# Sheet3.net
KiCad netlist of a schematic drawn in Altium Designer
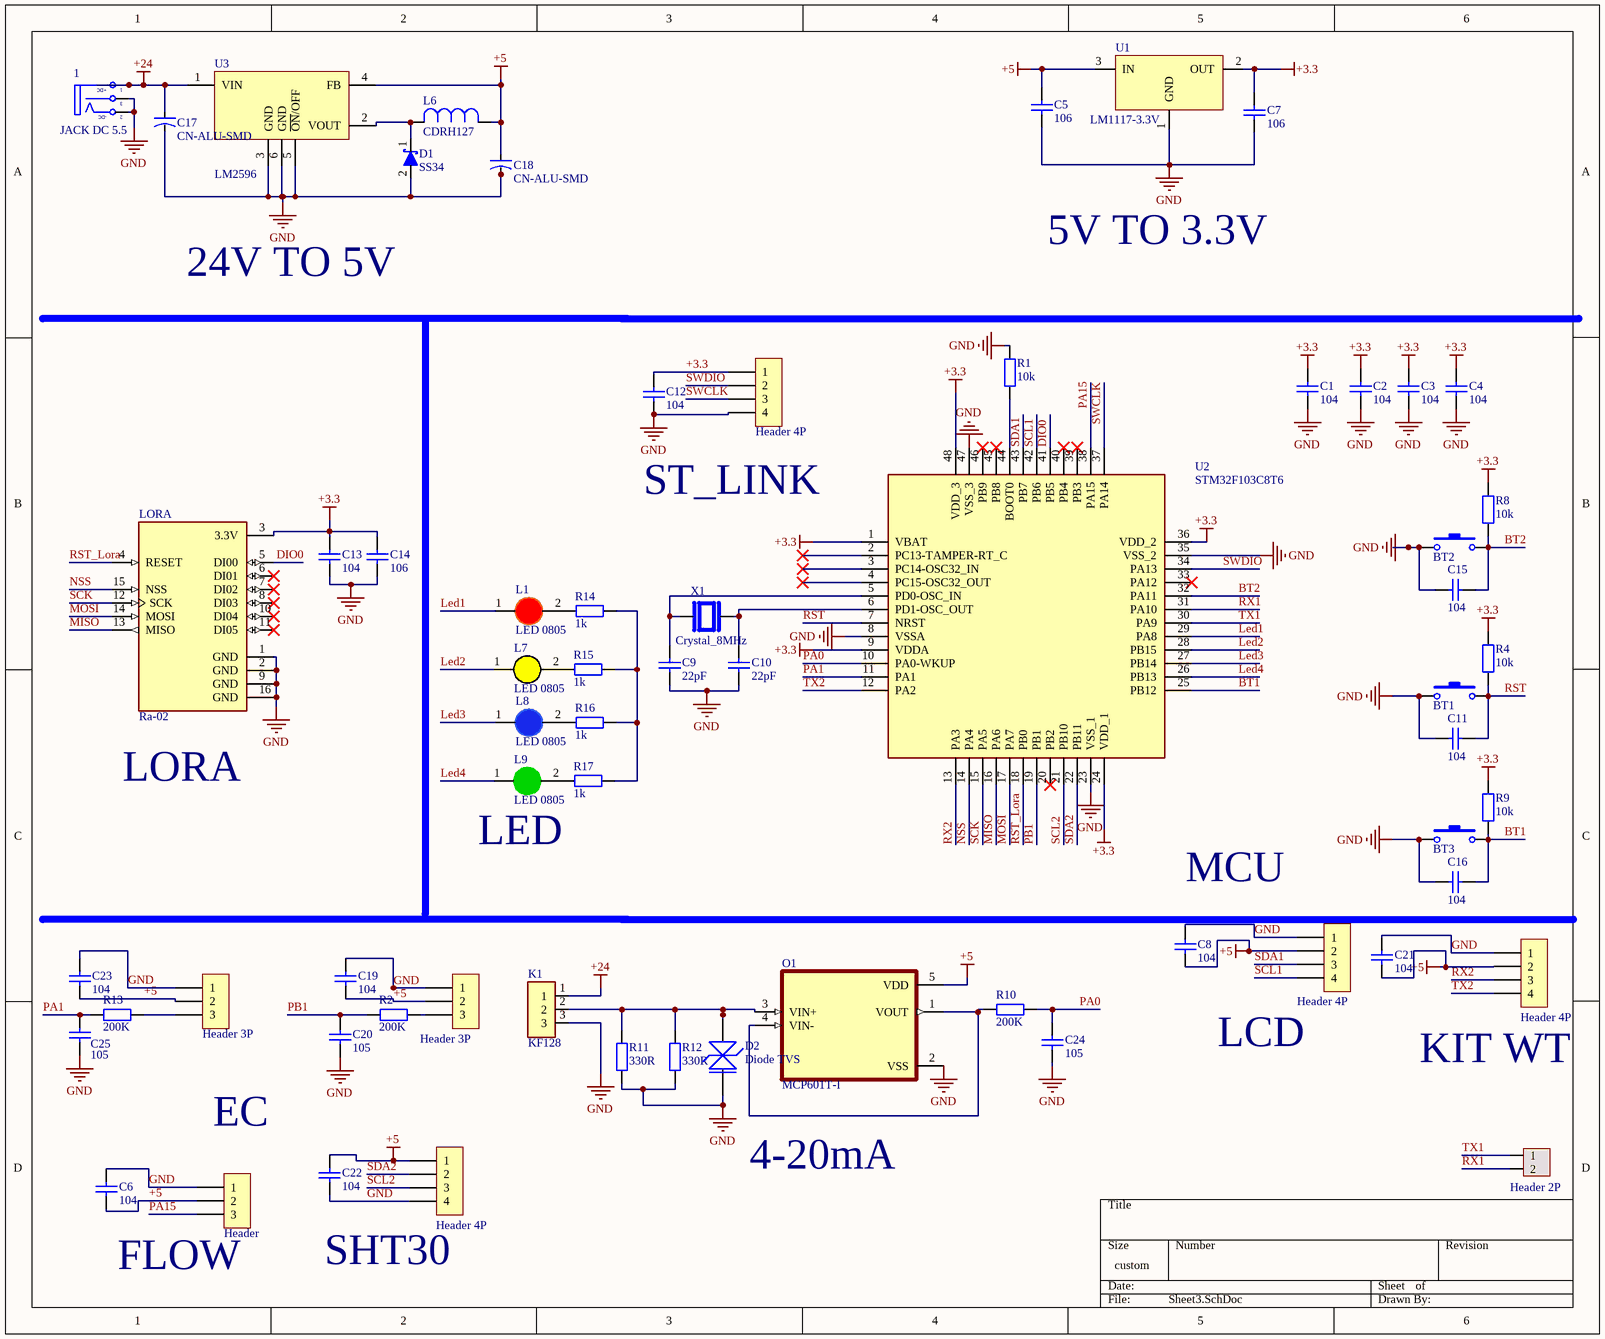
[diagram p0: Sheet3.SchDoc]

(export (version "E")
  (design (tool "Eeschema 10.0.6"))
  (components
    (comp (ref "1")
      (value "JACK DC 5.5")
      (footprint "JACK DC 5.5")
      (libsource (lib "Altium_Lib_by_KhueNguyenCreator") (part "JACK DC 5.5"))
    )
    (comp (ref "BT1")
      (value "Nut Nhan 2 Chan SMD 3x6x2.5")
      (footprint "Nut Nhan 2 Chan SMD 3x6x2.5")
      (libsource (lib "Altium_Lib_by_KhueNguyenCreator") (part "Nut Nhan 2 Chan SMD 3x6x2.5"))
    )
    (comp (ref "BT2")
      (value "Nut Nhan 2 Chan SMD 3x6x2.5")
      (footprint "Nut Nhan 2 Chan SMD 3x6x2.5")
      (libsource (lib "Altium_Lib_by_KhueNguyenCreator") (part "Nut Nhan 2 Chan SMD 3x6x2.5"))
    )
    (comp (ref "BT3")
      (value "Nut Nhan 2 Chan SMD 3x6x2.5")
      (footprint "Nut Nhan 2 Chan SMD 3x6x2.5")
      (libsource (lib "Altium_Lib_by_KhueNguyenCreator") (part "Nut Nhan 2 Chan SMD 3x6x2.5"))
    )
    (comp (ref "C1")
      (value "104")
      (footprint "tu 1206")
      (description "Dán")
      (libsource (lib "Altium_Lib_by_KhueNguyenCreator") (part "Tu 1206 104 50V 20%"))
    )
    (comp (ref "C2")
      (value "104")
      (footprint "tu 1206")
      (description "Dán")
      (libsource (lib "Altium_Lib_by_KhueNguyenCreator") (part "Tu 1206 104 50V 20%"))
    )
    (comp (ref "C3")
      (value "104")
      (footprint "tu 1206")
      (description "Dán")
      (libsource (lib "Altium_Lib_by_KhueNguyenCreator") (part "Tu 1206 104 50V 20%"))
    )
    (comp (ref "C4")
      (value "104")
      (footprint "tu 1206")
      (description "Dán")
      (libsource (lib "Altium_Lib_by_KhueNguyenCreator") (part "Tu 1206 104 50V 20%"))
    )
    (comp (ref "C5")
      (value "106")
      (footprint "tu 1206")
      (description "Dán")
      (libsource (lib "Altium_Lib_by_KhueNguyenCreator") (part "Tu 1206 106 16V 20%"))
    )
    (comp (ref "C6")
      (value "104")
      (footprint "tu 1206")
      (description "Dán")
      (libsource (lib "Altium_Lib_by_KhueNguyenCreator") (part "Tu 1206 104 50V 20%"))
    )
    (comp (ref "C7")
      (value "106")
      (footprint "tu 1206")
      (description "Dán")
      (libsource (lib "Altium_Lib_by_KhueNguyenCreator") (part "Tu 1206 106 16V 20%"))
    )
    (comp (ref "C8")
      (value "104")
      (footprint "tu 1206")
      (description "Dán")
      (libsource (lib "Altium_Lib_by_KhueNguyenCreator") (part "Tu 1206 104 50V 20%"))
    )
    (comp (ref "C9")
      (value "22pF")
      (footprint "tu 1206")
      (description "Dán")
      (libsource (lib "Altium_Lib_by_KhueNguyenCreator") (part "Tu 1206 104 50V 20%"))
    )
    (comp (ref "C10")
      (value "22pF")
      (footprint "tu 1206")
      (description "Dán")
      (libsource (lib "Altium_Lib_by_KhueNguyenCreator") (part "Tu 1206 104 50V 20%"))
    )
    (comp (ref "C11")
      (value "104")
      (footprint "tu 1206")
      (description "Dán")
      (libsource (lib "Altium_Lib_by_KhueNguyenCreator") (part "Tu 1206 104 50V 20%"))
    )
    (comp (ref "C12")
      (value "104")
      (footprint "tu 1206")
      (description "Dán")
      (libsource (lib "Altium_Lib_by_KhueNguyenCreator") (part "Tu 1206 104 50V 20%"))
    )
    (comp (ref "C13")
      (value "104")
      (footprint "tu 1206")
      (description "Dán")
      (libsource (lib "Altium_Lib_by_KhueNguyenCreator") (part "Tu 1206 104 50V 20%"))
    )
    (comp (ref "C14")
      (value "106")
      (footprint "tu 1206")
      (description "Dán")
      (libsource (lib "Altium_Lib_by_KhueNguyenCreator") (part "Tu 1206 106 16V 20%"))
    )
    (comp (ref "C15")
      (value "104")
      (footprint "tu 1206")
      (description "Dán")
      (libsource (lib "Altium_Lib_by_KhueNguyenCreator") (part "Tu 1206 104 50V 20%"))
    )
    (comp (ref "C16")
      (value "104")
      (footprint "tu 1206")
      (description "Dán")
      (libsource (lib "Altium_Lib_by_KhueNguyenCreator") (part "Tu 1206 104 50V 20%"))
    )
    (comp (ref "C17")
      (value "CN-ALU-SMD")
      (footprint "CAP-ALU-SMD-H")
      (description "Polarized Capacitor (Axial)")
      (fields (field (name "PUBLISHER") "Altium Limited"))
      (libsource (lib "TechMT.VN_Lib_Project v2") (part "CN-ALU-SMD"))
    )
    (comp (ref "C18")
      (value "CN-ALU-SMD")
      (footprint "CAP-ALU-SMD-D")
      (description "Polarized Capacitor (Axial)")
      (fields (field (name "PUBLISHER") "Altium Limited"))
      (libsource (lib "TechMT.VN_Lib_Project v2") (part "CN-ALU-SMD"))
    )
    (comp (ref "C19")
      (value "104")
      (footprint "tu 1206")
      (description "Dán")
      (libsource (lib "Altium_Lib_by_KhueNguyenCreator") (part "Tu 1206 104 50V 20%"))
    )
    (comp (ref "C20")
      (value "105")
      (footprint "tu 1206")
      (description "Dán")
      (libsource (lib "Altium_Lib_by_KhueNguyenCreator") (part "Tu 1206 105 50V 20%"))
    )
    (comp (ref "C21")
      (value "104")
      (footprint "tu 1206")
      (description "Dán")
      (libsource (lib "Altium_Lib_by_KhueNguyenCreator") (part "Tu 1206 104 50V 20%"))
    )
    (comp (ref "C22")
      (value "104")
      (footprint "tu 1206")
      (description "Dán")
      (libsource (lib "Altium_Lib_by_KhueNguyenCreator") (part "Tu 1206 104 50V 20%"))
    )
    (comp (ref "C23")
      (value "104")
      (footprint "tu 1206")
      (description "Dán")
      (libsource (lib "Altium_Lib_by_KhueNguyenCreator") (part "Tu 1206 104 50V 20%"))
    )
    (comp (ref "C24")
      (value "105")
      (footprint "tu 1206")
      (description "Dán")
      (libsource (lib "Altium_Lib_by_KhueNguyenCreator") (part "Tu 1206 105 50V 20%"))
    )
    (comp (ref "C25")
      (value "105")
      (footprint "tu 1206")
      (description "Dán")
      (libsource (lib "Altium_Lib_by_KhueNguyenCreator") (part "Tu 1206 105 50V 20%"))
    )
    (comp (ref "D1")
      (value "SS34")
      (footprint "DO-214AC")
      (description "Diode Schottky 40 V 5A Surface Mount DO-214AC (SMA)")
      (libsource (lib "My_lib") (part "SS54"))
    )
    (comp (ref "D2")
      (value "Diode TVS")
      (footprint "MinhTien_PCBLib:DO-214AC")
      (description "TVS Diodes - Transient Voltage Suppressors")
      (fields (field (name "PUBLISHER") "Altium Limited"))
      (libsource (lib "MinhTien_SCHLib") (part "Diode TVS"))
    )
    (comp (ref "FLOW")
      (value "Header")
      (footprint "XH2.54M-3")
      (description "Cắm")
      (libsource (lib "Altium_Lib_by_KhueNguyenCreator") (part "Header 3P 2.54 Duc Thang"))
    )
    (comp (ref "H1")
      (value "Header 2P")
      (footprint "XH2.54M-2")
      (description "Cắm")
      (libsource (lib "Altium_Lib_by_KhueNguyenCreator") (part "Header 2P 2.54 Duc Thang"))
    )
    (comp (ref "K1")
      (value "KF128")
      (footprint "KF128_3V")
      (description "KF128-3-V Domino 3 Chân Thẳng 2.54mm 150V 6A Hàn PCB")
      (libsource (lib "My_lib") (part "KF128_3V"))
    )
    (comp (ref "KIT")
      (value "Header 4P")
      (footprint "XH2.54M-4")
      (description "Cắm")
      (libsource (lib "Altium_Lib_by_KhueNguyenCreator") (part "Header 4P 2.54 Duc Thang"))
    )
    (comp (ref "L1")
      (value "LED 0805")
      (footprint "LED-1206-Red")
      (description "Dán")
      (libsource (lib "Altium_Lib_by_KhueNguyenCreator") (part "LED 1206 Do"))
    )
    (comp (ref "L6")
      (value "CDRH127")
      (footprint "33uH")
      (description "33uH - Inductor 4.2 A")
      (libsource (lib "My_lib") (part "CDRH127"))
    )
    (comp (ref "L7")
      (value "LED 0805")
      (footprint "LED-1206-Yellow")
      (description "Dán")
      (libsource (lib "Altium_Lib_by_KhueNguyenCreator") (part "LED 1206 Vang"))
    )
    (comp (ref "L8")
      (value "LED 0805")
      (footprint "LED-1206-Blue")
      (description "Dán")
      (libsource (lib "Altium_Lib_by_KhueNguyenCreator") (part "LED 1206 Xanh Duong"))
    )
    (comp (ref "L9")
      (value "LED 0805")
      (footprint "LED-1206-Green")
      (description "Dán")
      (libsource (lib "Altium_Lib_by_KhueNguyenCreator") (part "LED 1206 Xanh La"))
    )
    (comp (ref "LCD")
      (value "Header 4P")
      (footprint "XH2.54M-4")
      (description "Cắm")
      (libsource (lib "Altium_Lib_by_KhueNguyenCreator") (part "Header 4P 2.54 Duc Thang"))
    )
    (comp (ref "LORA")
      (value "Ra-02")
      (footprint "Sx1278")
      (description "Lora sx1278")
      (libsource (lib "My_lib") (part "Ra-02"))
    )
    (comp (ref "O1")
      (value "MCP601T-I")
      (footprint "MCP601T-I")
      (description "MCP601T-I/OT IC OPAMP General Purpose Amplifier 1 Circuit 2.8MHz, 5-SOT-23")
      (libsource (lib "My_lib") (part "MCP601T-I"))
    )
    (comp (ref "R1")
      (value "10k")
      (footprint "tro smd 1206")
      (description "Dán")
      (libsource (lib "Altium_Lib_by_KhueNguyenCreator") (part "Tro 1206 1% 10k"))
    )
    (comp (ref "R2")
      (value "200K")
      (footprint "tro smd 1206")
      (description "Dán")
      (libsource (lib "Altium_Lib_by_KhueNguyenCreator") (part "Tro 1206 5% 100K"))
    )
    (comp (ref "R4")
      (value "10k")
      (footprint "tro smd 1206")
      (description "Dán")
      (libsource (lib "Altium_Lib_by_KhueNguyenCreator") (part "Tro 1206 1% 10k"))
    )
    (comp (ref "R8")
      (value "10k")
      (footprint "tro smd 1206")
      (description "Dán")
      (libsource (lib "Altium_Lib_by_KhueNguyenCreator") (part "Tro 1206 1% 10k"))
    )
    (comp (ref "R9")
      (value "10k")
      (footprint "tro smd 1206")
      (description "Dán")
      (libsource (lib "Altium_Lib_by_KhueNguyenCreator") (part "Tro 1206 1% 10k"))
    )
    (comp (ref "R10")
      (value "200K")
      (footprint "tro smd 1206")
      (description "Dán")
      (libsource (lib "Altium_Lib_by_KhueNguyenCreator") (part "Tro 1206 5% 100K"))
    )
    (comp (ref "R11")
      (value "330R")
      (footprint "tro smd 1206")
      (description "Dán")
      (libsource (lib "Altium_Lib_by_KhueNguyenCreator") (part "Tro 1206 1% 10R"))
    )
    (comp (ref "R12")
      (value "330R")
      (footprint "tro smd 1206")
      (description "Dán")
      (libsource (lib "Altium_Lib_by_KhueNguyenCreator") (part "Tro 1206 1% 10R"))
    )
    (comp (ref "R13")
      (value "200K")
      (footprint "tro smd 1206")
      (description "Dán")
      (libsource (lib "Altium_Lib_by_KhueNguyenCreator") (part "Tro 1206 5% 100K"))
    )
    (comp (ref "R14")
      (value "1k")
      (footprint "Tro smd 1206")
      (description "Dán")
      (libsource (lib "Altium_Lib_by_KhueNguyenCreator") (part "Tro 1206 5% 390R"))
    )
    (comp (ref "R15")
      (value "1k")
      (footprint "Tro smd 1206")
      (description "Dán")
      (libsource (lib "Altium_Lib_by_KhueNguyenCreator") (part "Tro 1206 5% 390R"))
    )
    (comp (ref "R16")
      (value "1k")
      (footprint "Tro smd 1206")
      (description "Dán")
      (libsource (lib "Altium_Lib_by_KhueNguyenCreator") (part "Tro 1206 5% 390R"))
    )
    (comp (ref "R17")
      (value "1k")
      (footprint "Tro smd 1206")
      (description "Dán")
      (libsource (lib "Altium_Lib_by_KhueNguyenCreator") (part "Tro 1206 5% 390R"))
    )
    (comp (ref "SAL")
      (value "Header 3P")
      (footprint "XH2.54M-3")
      (description "Cắm")
      (libsource (lib "Altium_Lib_by_KhueNguyenCreator") (part "Header 3P 2.54 Duc Thang"))
    )
    (comp (ref "SHT3x")
      (value "Header 4P")
      (footprint "XH2.54M-4")
      (description "Cắm")
      (libsource (lib "Altium_Lib_by_KhueNguyenCreator") (part "Header 4P 2.54 Duc Thang"))
    )
    (comp (ref "ST")
      (value "Header 4P")
      (footprint "XH2.54M-4")
      (description "Cắm")
      (libsource (lib "Altium_Lib_by_KhueNguyenCreator") (part "Header 4P 2.54 Duc Thang"))
    )
    (comp (ref "TEMP_W")
      (value "Header 3P")
      (footprint "XH2.54M-3")
      (description "Cắm")
      (libsource (lib "Altium_Lib_by_KhueNguyenCreator") (part "Header 3P 2.54 Duc Thang"))
    )
    (comp (ref "U1")
      (value "LM1117-3.3V")
      (footprint "SOT223")
      (description "800mA Low-Dropout Linear Regulator")
      (fields (field (name "CREATOR") "Nguyen Ba Bien"))
      (libsource (lib "TechMT.VN_Lib_Project v2") (part "LM1117"))
    )
    (comp (ref "U2")
      (value "STM32F103C8T6")
      (footprint "LQFP-48_19.6_393_58X11_SMD")
      (description "ARM® Cortex®-M3 STM32F1 Microcontroller IC 32-Bit 72MHz 64KB (64K x 8) FLASH 48-LQFP (7x7)")
      (fields (field (name "MANUFACTURER") "STMicroelectronics"))
      (libsource (lib "Altium_Lib_by_KhueNguyenCreator") (part "IC_STM32F103C8T6"))
    )
    (comp (ref "U3")
      (value "LM2596")
      (footprint "MinhTien_PcbLib:TO263-5")
      (description "1A Regulator")
      (libsource (lib "MinhTien_SCHLib") (part "LM2596"))
    )
    (comp (ref "X1")
      (value "Crystal_8MHz")
      (footprint "XTAL_8MHz")
      (description "8MHz")
      (libsource (lib "My_lib") (part "Crystal_8MHz"))
    )
  )
  (nets
    (net (code "1") (name "+3.3") (class "Default")
      (node (ref "C1") (pin "1") (pinfunction "1_1") (pintype "passive"))
      (node (ref "C12") (pin "2") (pinfunction "2_2") (pintype "passive"))
      (node (ref "C13") (pin "1") (pinfunction "1_1") (pintype "passive"))
      (node (ref "C14") (pin "1") (pinfunction "1_1") (pintype "passive"))
      (node (ref "C2") (pin "1") (pinfunction "1_1") (pintype "passive"))
      (node (ref "C3") (pin "1") (pinfunction "1_1") (pintype "passive"))
      (node (ref "C4") (pin "1") (pinfunction "1_1") (pintype "passive"))
      (node (ref "C7") (pin "1") (pinfunction "1_1") (pintype "passive"))
      (node (ref "LORA") (pin "3") (pinfunction "3.3V_3") (pintype "power_in"))
      (node (ref "R4") (pin "2") (pinfunction "2_2") (pintype "passive"))
      (node (ref "R8") (pin "2") (pinfunction "2_2") (pintype "passive"))
      (node (ref "R9") (pin "2") (pinfunction "2_2") (pintype "passive"))
      (node (ref "ST") (pin "1") (pinfunction "1_1") (pintype "passive"))
      (node (ref "U1") (pin "2") (pinfunction "OUT_2") (pintype "passive"))
      (node (ref "U2") (pin "1") (pinfunction "VBAT_1") (pintype "passive"))
      (node (ref "U2") (pin "24") (pinfunction "VDD_1_24") (pintype "passive"))
      (node (ref "U2") (pin "36") (pinfunction "VDD_2_36") (pintype "passive"))
      (node (ref "U2") (pin "48") (pinfunction "VDD_3_48") (pintype "passive"))
      (node (ref "U2") (pin "9") (pinfunction "VDDA_9") (pintype "passive"))
    )
    (net (code "2") (name "+5") (class "Default")
      (node (ref "C18") (pin "1") (pinfunction "1_1") (pintype "passive"))
      (node (ref "C19") (pin "2") (pinfunction "2_2") (pintype "passive"))
      (node (ref "C21") (pin "2") (pinfunction "2_2") (pintype "passive"))
      (node (ref "C22") (pin "1") (pinfunction "1_1") (pintype "passive"))
      (node (ref "C23") (pin "2") (pinfunction "2_2") (pintype "passive"))
      (node (ref "C5") (pin "1") (pinfunction "1_1") (pintype "passive"))
      (node (ref "C6") (pin "2") (pinfunction "2_2") (pintype "passive"))
      (node (ref "C8") (pin "2") (pinfunction "2_2") (pintype "passive"))
      (node (ref "FLOW") (pin "2") (pinfunction "2_2") (pintype "passive"))
      (node (ref "KIT") (pin "2") (pinfunction "2_2") (pintype "passive"))
      (node (ref "L6") (pin "1") (pinfunction "1_1") (pintype "passive"))
      (node (ref "LCD") (pin "2") (pinfunction "2_2") (pintype "passive"))
      (node (ref "O1") (pin "5") (pinfunction "VDD_5") (pintype "power_in"))
      (node (ref "SAL") (pin "2") (pinfunction "2_2") (pintype "passive"))
      (node (ref "SHT3x") (pin "1") (pinfunction "1_1") (pintype "passive"))
      (node (ref "TEMP_W") (pin "2") (pinfunction "2_2") (pintype "passive"))
      (node (ref "U1") (pin "3") (pinfunction "IN_3") (pintype "passive"))
      (node (ref "U3") (pin "4") (pinfunction "FB_4") (pintype "passive"))
    )
    (net (code "3") (name "+24") (class "Default")
      (node (ref "1") (pin "1") (pinfunction "T_1") (pintype "passive"))
      (node (ref "C17") (pin "1") (pinfunction "1_1") (pintype "passive"))
      (node (ref "K1") (pin "1") (pinfunction "1_1") (pintype "passive"))
      (node (ref "U3") (pin "1") (pinfunction "VIN_1") (pintype "passive"))
    )
    (net (code "4") (name "/BT1") (class "Default")
      (node (ref "BT3") (pin "2") (pinfunction "2_2") (pintype "passive"))
      (node (ref "C16") (pin "2") (pinfunction "2_2") (pintype "passive"))
      (node (ref "R9") (pin "1") (pinfunction "1_1") (pintype "passive"))
      (node (ref "U2") (pin "25") (pinfunction "PB12_25") (pintype "passive"))
    )
    (net (code "5") (name "/BT2") (class "Default")
      (node (ref "BT2") (pin "2") (pinfunction "2_2") (pintype "passive"))
      (node (ref "C15") (pin "2") (pinfunction "2_2") (pintype "passive"))
      (node (ref "R8") (pin "1") (pinfunction "1_1") (pintype "passive"))
      (node (ref "U2") (pin "32") (pinfunction "PA11_32") (pintype "passive"))
    )
    (net (code "6") (name "/DIO0") (class "Default")
      (node (ref "LORA") (pin "5") (pinfunction "DI00_5") (pintype "bidirectional"))
      (node (ref "U2") (pin "41") (pinfunction "PB5_41") (pintype "passive"))
    )
    (net (code "7") (name "/Led1") (class "Default")
      (node (ref "L1") (pin "1") (pinfunction "A_1") (pintype "passive"))
      (node (ref "U2") (pin "29") (pinfunction "PA8_29") (pintype "passive"))
    )
    (net (code "8") (name "/Led2") (class "Default")
      (node (ref "L7") (pin "1") (pinfunction "A_1") (pintype "passive"))
      (node (ref "U2") (pin "28") (pinfunction "PB15_28") (pintype "passive"))
    )
    (net (code "9") (name "/Led3") (class "Default")
      (node (ref "L8") (pin "1") (pinfunction "A_1") (pintype "passive"))
      (node (ref "U2") (pin "27") (pinfunction "PB14_27") (pintype "passive"))
    )
    (net (code "10") (name "/Led4") (class "Default")
      (node (ref "L9") (pin "1") (pinfunction "A_1") (pintype "passive"))
      (node (ref "U2") (pin "26") (pinfunction "PB13_26") (pintype "passive"))
    )
    (net (code "11") (name "/MISO") (class "Default")
      (node (ref "LORA") (pin "13") (pinfunction "MISO_13") (pintype "output"))
      (node (ref "U2") (pin "16") (pinfunction "PA6_16") (pintype "passive"))
    )
    (net (code "12") (name "/MOSI") (class "Default")
      (node (ref "LORA") (pin "14") (pinfunction "MOSI_14") (pintype "input"))
      (node (ref "U2") (pin "17") (pinfunction "PA7_17") (pintype "passive"))
    )
    (net (code "13") (name "/NSS") (class "Default")
      (node (ref "LORA") (pin "15") (pinfunction "NSS_15") (pintype "input"))
      (node (ref "U2") (pin "14") (pinfunction "PA4_14") (pintype "passive"))
    )
    (net (code "14") (name "/PA0") (class "Default")
      (node (ref "C24") (pin "1") (pinfunction "1_1") (pintype "passive"))
      (node (ref "R10") (pin "2") (pinfunction "2_2") (pintype "passive"))
      (node (ref "U2") (pin "10") (pinfunction "PA0-WKUP_10") (pintype "passive"))
    )
    (net (code "15") (name "/PA1") (class "Default")
      (node (ref "C25") (pin "1") (pinfunction "1_1") (pintype "passive"))
      (node (ref "R13") (pin "1") (pinfunction "1_1") (pintype "passive"))
      (node (ref "U2") (pin "11") (pinfunction "PA1_11") (pintype "passive"))
    )
    (net (code "16") (name "/PA15") (class "Default")
      (node (ref "FLOW") (pin "3") (pinfunction "3_3") (pintype "passive"))
      (node (ref "U2") (pin "38") (pinfunction "PA15_38") (pintype "passive"))
    )
    (net (code "17") (name "/PB1") (class "Default")
      (node (ref "C20") (pin "1") (pinfunction "1_1") (pintype "passive"))
      (node (ref "R2") (pin "1") (pinfunction "1_1") (pintype "passive"))
      (node (ref "U2") (pin "19") (pinfunction "PB1_19") (pintype "passive"))
    )
    (net (code "18") (name "/RST") (class "Default")
      (node (ref "BT1") (pin "2") (pinfunction "2_2") (pintype "passive"))
      (node (ref "C11") (pin "2") (pinfunction "2_2") (pintype "passive"))
      (node (ref "R4") (pin "1") (pinfunction "1_1") (pintype "passive"))
      (node (ref "U2") (pin "7") (pinfunction "NRST_7") (pintype "passive"))
    )
    (net (code "19") (name "/RST_Lora") (class "Default")
      (node (ref "LORA") (pin "4") (pinfunction "RESET_4") (pintype "input"))
      (node (ref "U2") (pin "18") (pinfunction "PB0_18") (pintype "passive"))
    )
    (net (code "20") (name "/RX1") (class "Default")
      (node (ref "H1") (pin "2") (pinfunction "2_2") (pintype "passive"))
      (node (ref "U2") (pin "31") (pinfunction "PA10_31") (pintype "passive"))
    )
    (net (code "21") (name "/RX2") (class "Default")
      (node (ref "KIT") (pin "3") (pinfunction "3_3") (pintype "passive"))
      (node (ref "U2") (pin "13") (pinfunction "PA3_13") (pintype "passive"))
    )
    (net (code "22") (name "/SCK") (class "Default")
      (node (ref "LORA") (pin "12") (pinfunction "SCK_12") (pintype "input"))
      (node (ref "U2") (pin "15") (pinfunction "PA5_15") (pintype "passive"))
    )
    (net (code "23") (name "/SCL1") (class "Default")
      (node (ref "LCD") (pin "4") (pinfunction "4_4") (pintype "passive"))
      (node (ref "U2") (pin "42") (pinfunction "PB6_42") (pintype "passive"))
    )
    (net (code "24") (name "/SCL2") (class "Default")
      (node (ref "SHT3x") (pin "3") (pinfunction "3_3") (pintype "passive"))
      (node (ref "U2") (pin "21") (pinfunction "PB10_21") (pintype "passive"))
    )
    (net (code "25") (name "/SDA1") (class "Default")
      (node (ref "LCD") (pin "3") (pinfunction "3_3") (pintype "passive"))
      (node (ref "U2") (pin "43") (pinfunction "PB7_43") (pintype "passive"))
    )
    (net (code "26") (name "/SDA2") (class "Default")
      (node (ref "SHT3x") (pin "2") (pinfunction "2_2") (pintype "passive"))
      (node (ref "U2") (pin "22") (pinfunction "PB11_22") (pintype "passive"))
    )
    (net (code "27") (name "/SWCLK") (class "Default")
      (node (ref "ST") (pin "3") (pinfunction "3_3") (pintype "passive"))
      (node (ref "U2") (pin "37") (pinfunction "PA14_37") (pintype "passive"))
    )
    (net (code "28") (name "/SWDIO") (class "Default")
      (node (ref "ST") (pin "2") (pinfunction "2_2") (pintype "passive"))
      (node (ref "U2") (pin "34") (pinfunction "PA13_34") (pintype "passive"))
    )
    (net (code "29") (name "/TX1") (class "Default")
      (node (ref "H1") (pin "1") (pinfunction "1_1") (pintype "passive"))
      (node (ref "U2") (pin "30") (pinfunction "PA9_30") (pintype "passive"))
    )
    (net (code "30") (name "/TX2") (class "Default")
      (node (ref "KIT") (pin "4") (pinfunction "4_4") (pintype "passive"))
      (node (ref "U2") (pin "12") (pinfunction "PA2_12") (pintype "passive"))
    )
    (net (code "31") (name "GND") (class "Default")
      (node (ref "1") (pin "2") (pinfunction "TN_2") (pintype "passive"))
      (node (ref "1") (pin "3") (pinfunction "S_3") (pintype "power_in"))
      (node (ref "BT1") (pin "1") (pinfunction "1_1") (pintype "passive"))
      (node (ref "BT2") (pin "1") (pinfunction "1_1") (pintype "passive"))
      (node (ref "BT3") (pin "1") (pinfunction "1_1") (pintype "passive"))
      (node (ref "C1") (pin "2") (pinfunction "2_2") (pintype "passive"))
      (node (ref "C10") (pin "2") (pinfunction "2_2") (pintype "passive"))
      (node (ref "C11") (pin "1") (pinfunction "1_1") (pintype "passive"))
      (node (ref "C12") (pin "1") (pinfunction "1_1") (pintype "passive"))
      (node (ref "C13") (pin "2") (pinfunction "2_2") (pintype "passive"))
      (node (ref "C14") (pin "2") (pinfunction "2_2") (pintype "passive"))
      (node (ref "C15") (pin "1") (pinfunction "1_1") (pintype "passive"))
      (node (ref "C16") (pin "1") (pinfunction "1_1") (pintype "passive"))
      (node (ref "C17") (pin "2") (pinfunction "2_2") (pintype "passive"))
      (node (ref "C18") (pin "2") (pinfunction "2_2") (pintype "passive"))
      (node (ref "C19") (pin "1") (pinfunction "1_1") (pintype "passive"))
      (node (ref "C2") (pin "2") (pinfunction "2_2") (pintype "passive"))
      (node (ref "C20") (pin "2") (pinfunction "2_2") (pintype "passive"))
      (node (ref "C21") (pin "1") (pinfunction "1_1") (pintype "passive"))
      (node (ref "C22") (pin "2") (pinfunction "2_2") (pintype "passive"))
      (node (ref "C23") (pin "1") (pinfunction "1_1") (pintype "passive"))
      (node (ref "C24") (pin "2") (pinfunction "2_2") (pintype "passive"))
      (node (ref "C25") (pin "2") (pinfunction "2_2") (pintype "passive"))
      (node (ref "C3") (pin "2") (pinfunction "2_2") (pintype "passive"))
      (node (ref "C4") (pin "2") (pinfunction "2_2") (pintype "passive"))
      (node (ref "C5") (pin "2") (pinfunction "2_2") (pintype "passive"))
      (node (ref "C6") (pin "1") (pinfunction "1_1") (pintype "passive"))
      (node (ref "C7") (pin "2") (pinfunction "2_2") (pintype "passive"))
      (node (ref "C8") (pin "1") (pinfunction "1_1") (pintype "passive"))
      (node (ref "C9") (pin "2") (pinfunction "2_2") (pintype "passive"))
      (node (ref "D1") (pin "2") (pinfunction "A_2") (pintype "bidirectional"))
      (node (ref "D2") (pin "2") (pinfunction "2_2") (pintype "power_in"))
      (node (ref "FLOW") (pin "1") (pinfunction "1_1") (pintype "passive"))
      (node (ref "K1") (pin "3") (pinfunction "3_3") (pintype "passive"))
      (node (ref "KIT") (pin "1") (pinfunction "1_1") (pintype "passive"))
      (node (ref "LCD") (pin "1") (pinfunction "1_1") (pintype "passive"))
      (node (ref "LORA") (pin "1") (pinfunction "GND_1") (pintype "power_in"))
      (node (ref "LORA") (pin "16") (pinfunction "GND_16") (pintype "power_in"))
      (node (ref "LORA") (pin "2") (pinfunction "GND_2") (pintype "power_in"))
      (node (ref "LORA") (pin "9") (pinfunction "GND_9") (pintype "power_in"))
      (node (ref "O1") (pin "2") (pinfunction "VSS_2") (pintype "power_in"))
      (node (ref "R1") (pin "2") (pinfunction "2_2") (pintype "passive"))
      (node (ref "R11") (pin "2") (pinfunction "2_2") (pintype "passive"))
      (node (ref "R12") (pin "2") (pinfunction "2_2") (pintype "passive"))
      (node (ref "SAL") (pin "1") (pinfunction "1_1") (pintype "passive"))
      (node (ref "SHT3x") (pin "4") (pinfunction "4_4") (pintype "passive"))
      (node (ref "ST") (pin "4") (pinfunction "4_4") (pintype "passive"))
      (node (ref "TEMP_W") (pin "1") (pinfunction "1_1") (pintype "passive"))
      (node (ref "U1") (pin "1") (pinfunction "GND_1") (pintype "passive"))
      (node (ref "U2") (pin "23") (pinfunction "VSS_1_23") (pintype "passive"))
      (node (ref "U2") (pin "35") (pinfunction "VSS_2_35") (pintype "passive"))
      (node (ref "U2") (pin "47") (pinfunction "VSS_3_47") (pintype "passive"))
      (node (ref "U2") (pin "8") (pinfunction "VSSA_8") (pintype "passive"))
      (node (ref "U3") (pin "3") (pinfunction "GND_3") (pintype "passive"))
      (node (ref "U3") (pin "5") (pinfunction "~{ON}/OFF_5") (pintype "passive"))
      (node (ref "U3") (pin "6") (pinfunction "GND_6") (pintype "passive"))
    )
    (net (code "32") (name "Net-(D1-K)") (class "Default")
      (node (ref "D1") (pin "1") (pinfunction "K_1") (pintype "bidirectional"))
      (node (ref "L6") (pin "2") (pinfunction "2_2") (pintype "passive"))
      (node (ref "U3") (pin "2") (pinfunction "VOUT_2") (pintype "passive"))
    )
    (net (code "33") (name "Net-(L1-K)") (class "Default")
      (node (ref "L1") (pin "2") (pinfunction "K_2") (pintype "passive"))
      (node (ref "R14") (pin "2") (pinfunction "2_2") (pintype "passive"))
    )
    (net (code "34") (name "Net-(L7-K)") (class "Default")
      (node (ref "L7") (pin "2") (pinfunction "K_2") (pintype "passive"))
      (node (ref "R15") (pin "1") (pinfunction "1_1") (pintype "passive"))
    )
    (net (code "35") (name "Net-(L8-K)") (class "Default")
      (node (ref "L8") (pin "2") (pinfunction "K_2") (pintype "passive"))
      (node (ref "R16") (pin "1") (pinfunction "1_1") (pintype "passive"))
    )
    (net (code "36") (name "Net-(L9-K)") (class "Default")
      (node (ref "L9") (pin "2") (pinfunction "K_2") (pintype "passive"))
      (node (ref "R17") (pin "1") (pinfunction "1_1") (pintype "passive"))
    )
    (net (code "37") (name "Net-(O1-VIN+)") (class "Default")
      (node (ref "D2") (pin "1") (pinfunction "1_1") (pintype "power_in"))
      (node (ref "K1") (pin "2") (pinfunction "2_2") (pintype "passive"))
      (node (ref "O1") (pin "3") (pinfunction "VIN+_3") (pintype "input"))
      (node (ref "R11") (pin "1") (pinfunction "1_1") (pintype "passive"))
      (node (ref "R12") (pin "1") (pinfunction "1_1") (pintype "passive"))
    )
    (net (code "38") (name "Net-(O1-VIN-)") (class "Default")
      (node (ref "O1") (pin "1") (pinfunction "VOUT_1") (pintype "output"))
      (node (ref "O1") (pin "4") (pinfunction "VIN-_4") (pintype "input"))
      (node (ref "R10") (pin "1") (pinfunction "1_1") (pintype "passive"))
    )
    (net (code "39") (name "Net-(R2-Pad2)") (class "Default")
      (node (ref "R2") (pin "2") (pinfunction "2_2") (pintype "passive"))
      (node (ref "SAL") (pin "3") (pinfunction "3_3") (pintype "passive"))
    )
    (net (code "40") (name "Net-(R13-Pad2)") (class "Default")
      (node (ref "R13") (pin "2") (pinfunction "2_2") (pintype "passive"))
      (node (ref "TEMP_W") (pin "3") (pinfunction "3_3") (pintype "passive"))
    )
    (net (code "41") (name "Net-(R14-Pad1)") (class "Default")
      (node (ref "R14") (pin "1") (pinfunction "1_1") (pintype "passive"))
      (node (ref "R15") (pin "2") (pinfunction "2_2") (pintype "passive"))
      (node (ref "R16") (pin "2") (pinfunction "2_2") (pintype "passive"))
      (node (ref "R17") (pin "2") (pinfunction "2_2") (pintype "passive"))
    )
    (net (code "42") (name "Net-(U2-BOOT0)") (class "Default")
      (node (ref "R1") (pin "1") (pinfunction "1_1") (pintype "passive"))
      (node (ref "U2") (pin "44") (pinfunction "BOOT0_44") (pintype "passive"))
    )
    (net (code "43") (name "Net-(U2-PD0-OSC_IN)") (class "Default")
      (node (ref "C9") (pin "1") (pinfunction "1_1") (pintype "passive"))
      (node (ref "U2") (pin "5") (pinfunction "PD0-OSC_IN_5") (pintype "passive"))
      (node (ref "X1") (pin "1") (pinfunction "1_1") (pintype "passive"))
    )
    (net (code "44") (name "Net-(U2-PD1-OSC_OUT)") (class "Default")
      (node (ref "C10") (pin "1") (pinfunction "1_1") (pintype "passive"))
      (node (ref "U2") (pin "6") (pinfunction "PD1-OSC_OUT_6") (pintype "passive"))
      (node (ref "X1") (pin "2") (pinfunction "2_2") (pintype "passive"))
    )
    (net (code "45") (name "unconnected-(LORA-DI01-Pad6)") (class "Default")
      (node (ref "LORA") (pin "6") (pinfunction "DI01_6") (pintype "bidirectional+no_connect"))
    )
    (net (code "46") (name "unconnected-(LORA-DI02-Pad7)") (class "Default")
      (node (ref "LORA") (pin "7") (pinfunction "DI02_7") (pintype "bidirectional+no_connect"))
    )
    (net (code "47") (name "unconnected-(LORA-DI03-Pad8)") (class "Default")
      (node (ref "LORA") (pin "8") (pinfunction "DI03_8") (pintype "bidirectional+no_connect"))
    )
    (net (code "48") (name "unconnected-(LORA-DI04-Pad10)") (class "Default")
      (node (ref "LORA") (pin "10") (pinfunction "DI04_10") (pintype "bidirectional+no_connect"))
    )
    (net (code "49") (name "unconnected-(LORA-DI05-Pad11)") (class "Default")
      (node (ref "LORA") (pin "11") (pinfunction "DI05_11") (pintype "bidirectional+no_connect"))
    )
    (net (code "50") (name "unconnected-(U2-PA12-Pad33)") (class "Default")
      (node (ref "U2") (pin "33") (pinfunction "PA12_33") (pintype "passive+no_connect"))
    )
    (net (code "51") (name "unconnected-(U2-PB2-Pad20)") (class "Default")
      (node (ref "U2") (pin "20") (pinfunction "PB2_20") (pintype "passive+no_connect"))
    )
    (net (code "52") (name "unconnected-(U2-PB3-Pad39)") (class "Default")
      (node (ref "U2") (pin "39") (pinfunction "PB3_39") (pintype "passive+no_connect"))
    )
    (net (code "53") (name "unconnected-(U2-PB4-Pad40)") (class "Default")
      (node (ref "U2") (pin "40") (pinfunction "PB4_40") (pintype "passive+no_connect"))
    )
    (net (code "54") (name "unconnected-(U2-PB8-Pad45)") (class "Default")
      (node (ref "U2") (pin "45") (pinfunction "PB8_45") (pintype "passive+no_connect"))
    )
    (net (code "55") (name "unconnected-(U2-PB9-Pad46)") (class "Default")
      (node (ref "U2") (pin "46") (pinfunction "PB9_46") (pintype "passive+no_connect"))
    )
    (net (code "56") (name "unconnected-(U2-PC13-TAMPER-RT_C-Pad2)") (class "Default")
      (node (ref "U2") (pin "2") (pinfunction "PC13-TAMPER-RT_C_2") (pintype "passive+no_connect"))
    )
    (net (code "57") (name "unconnected-(U2-PC14-OSC32_IN-Pad3)") (class "Default")
      (node (ref "U2") (pin "3") (pinfunction "PC14-OSC32_IN_3") (pintype "passive+no_connect"))
    )
    (net (code "58") (name "unconnected-(U2-PC15-OSC32_OUT-Pad4)") (class "Default")
      (node (ref "U2") (pin "4") (pinfunction "PC15-OSC32_OUT_4") (pintype "passive+no_connect"))
    )
  )
)
